# schematic.net
KiCad netlist of a schematic drawn in EAGLE
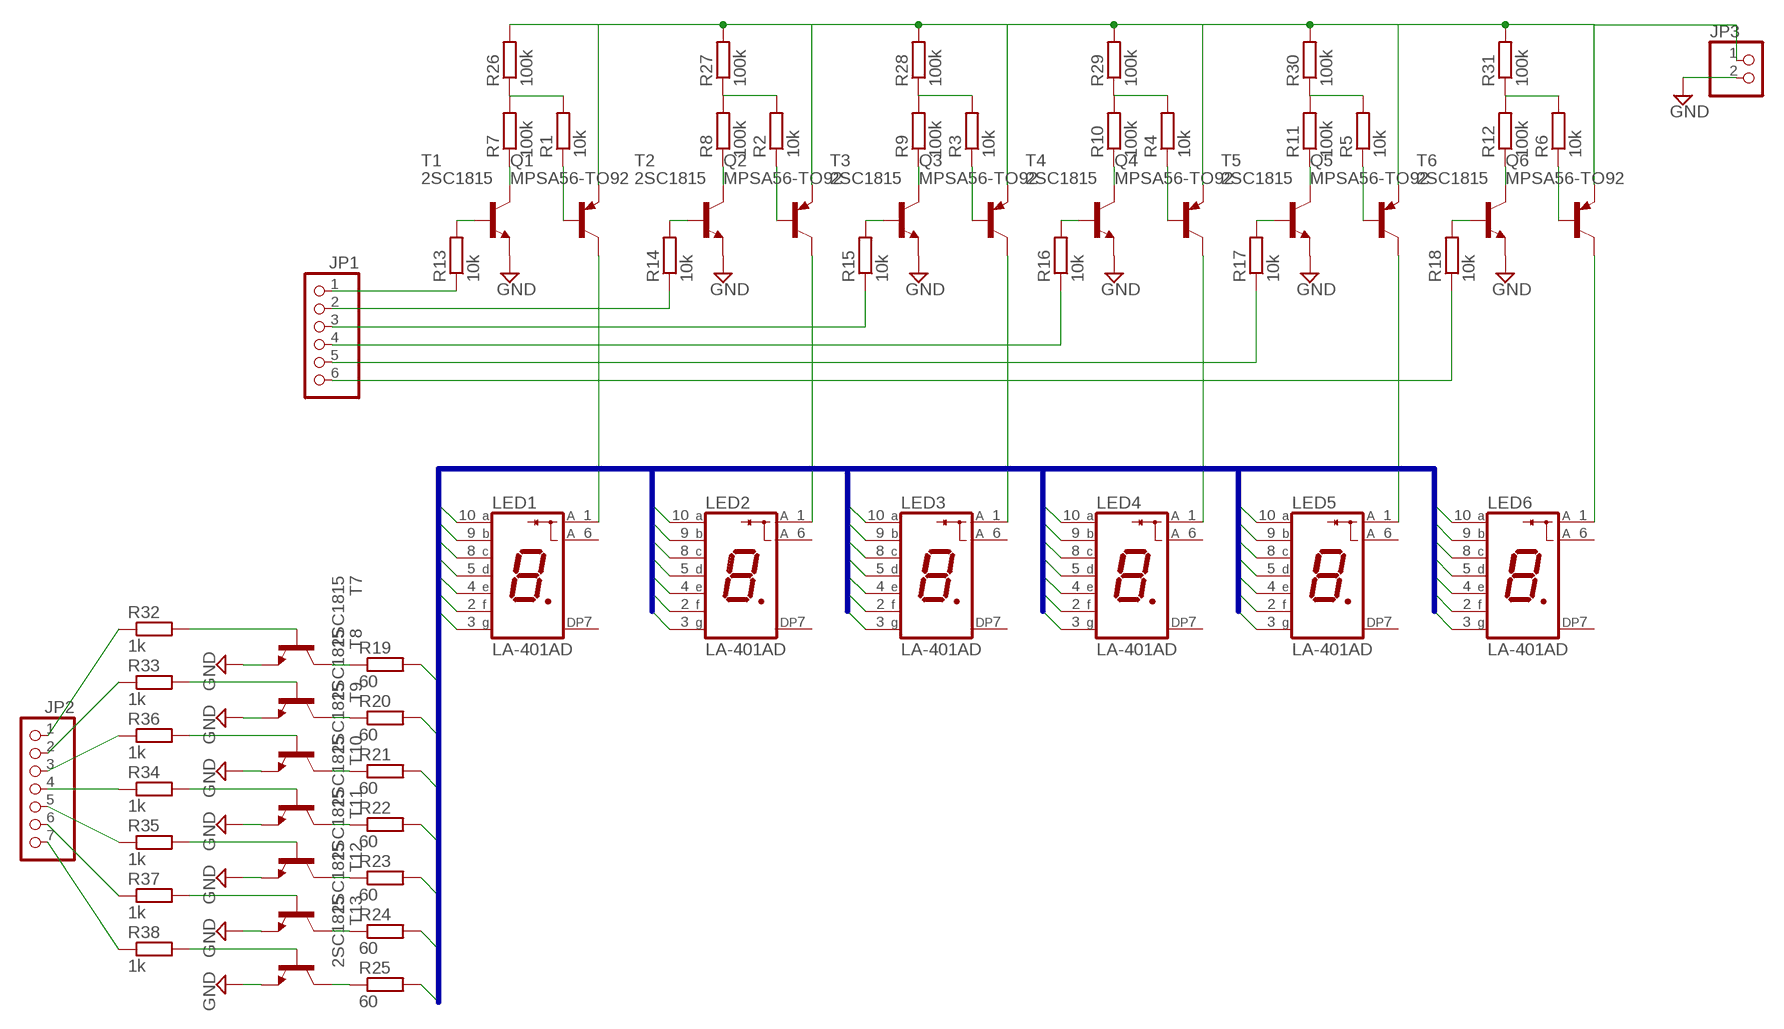
[diagram p0: schematic, sheet 1]

(export (version "E")
  (design (tool "Eeschema 10.0.6"))
  (components
    (comp (ref "JP1")
      (value "PINHD-1X6")
      (footprint "eagle-import:1X06")
      (libsource (lib "eagle-import") (part "PINHD-1X6"))
    )
    (comp (ref "JP2")
      (value "PINHD-1X7")
      (footprint "eagle-import:1X07")
      (libsource (lib "eagle-import") (part "PINHD-1X7"))
    )
    (comp (ref "JP3")
      (value "PINHD-1X2")
      (footprint "eagle-import:1X02")
      (libsource (lib "eagle-import") (part "PINHD-1X2"))
    )
    (comp (ref "LED1")
      (value "LA-401AD")
      (footprint "eagle-import:LA-401")
      (libsource (lib "eagle-import") (part "LA-401DA"))
    )
    (comp (ref "LED2")
      (value "LA-401AD")
      (footprint "eagle-import:LA-401")
      (libsource (lib "eagle-import") (part "LA-401DA"))
    )
    (comp (ref "LED3")
      (value "LA-401AD")
      (footprint "eagle-import:LA-401")
      (libsource (lib "eagle-import") (part "LA-401DA"))
    )
    (comp (ref "LED4")
      (value "LA-401AD")
      (footprint "eagle-import:LA-401")
      (libsource (lib "eagle-import") (part "LA-401DA"))
    )
    (comp (ref "LED5")
      (value "LA-401AD")
      (footprint "eagle-import:LA-401")
      (libsource (lib "eagle-import") (part "LA-401DA"))
    )
    (comp (ref "LED6")
      (value "LA-401AD")
      (footprint "eagle-import:LA-401")
      (libsource (lib "eagle-import") (part "LA-401DA"))
    )
    (comp (ref "Q1")
      (value "MPSA56-TO92")
      (footprint "eagle-import:TO92-CBE")
      (libsource (lib "eagle-import") (part "-?TO92MPSA56"))
    )
    (comp (ref "Q2")
      (value "MPSA56-TO92")
      (footprint "eagle-import:TO92-CBE")
      (libsource (lib "eagle-import") (part "-?TO92MPSA56"))
    )
    (comp (ref "Q3")
      (value "MPSA56-TO92")
      (footprint "eagle-import:TO92-CBE")
      (libsource (lib "eagle-import") (part "-?TO92MPSA56"))
    )
    (comp (ref "Q4")
      (value "MPSA56-TO92")
      (footprint "eagle-import:TO92-CBE")
      (libsource (lib "eagle-import") (part "-?TO92MPSA56"))
    )
    (comp (ref "Q5")
      (value "MPSA56-TO92")
      (footprint "eagle-import:TO92-CBE")
      (libsource (lib "eagle-import") (part "-?TO92MPSA56"))
    )
    (comp (ref "Q6")
      (value "MPSA56-TO92")
      (footprint "eagle-import:TO92-CBE")
      (libsource (lib "eagle-import") (part "-?TO92MPSA56"))
    )
    (comp (ref "R1")
      (value "10k")
      (footprint "eagle-import:0204_5")
      (libsource (lib "eagle-import") (part "R-EU_0204/5"))
    )
    (comp (ref "R2")
      (value "10k")
      (footprint "eagle-import:0204_5")
      (libsource (lib "eagle-import") (part "R-EU_0204/5"))
    )
    (comp (ref "R3")
      (value "10k")
      (footprint "eagle-import:0204_5")
      (libsource (lib "eagle-import") (part "R-EU_0204/5"))
    )
    (comp (ref "R4")
      (value "10k")
      (footprint "eagle-import:0204_5")
      (libsource (lib "eagle-import") (part "R-EU_0204/5"))
    )
    (comp (ref "R5")
      (value "10k")
      (footprint "eagle-import:0204_5")
      (libsource (lib "eagle-import") (part "R-EU_0204/5"))
    )
    (comp (ref "R6")
      (value "10k")
      (footprint "eagle-import:0204_5")
      (libsource (lib "eagle-import") (part "R-EU_0204/5"))
    )
    (comp (ref "R7")
      (value "100k")
      (footprint "eagle-import:0204_5")
      (libsource (lib "eagle-import") (part "R-EU_0204/5"))
    )
    (comp (ref "R8")
      (value "100k")
      (footprint "eagle-import:0204_5")
      (libsource (lib "eagle-import") (part "R-EU_0204/5"))
    )
    (comp (ref "R9")
      (value "100k")
      (footprint "eagle-import:0204_5")
      (libsource (lib "eagle-import") (part "R-EU_0204/5"))
    )
    (comp (ref "R10")
      (value "100k")
      (footprint "eagle-import:0204_5")
      (libsource (lib "eagle-import") (part "R-EU_0204/5"))
    )
    (comp (ref "R11")
      (value "100k")
      (footprint "eagle-import:0204_5")
      (libsource (lib "eagle-import") (part "R-EU_0204/5"))
    )
    (comp (ref "R12")
      (value "100k")
      (footprint "eagle-import:0204_5")
      (libsource (lib "eagle-import") (part "R-EU_0204/5"))
    )
    (comp (ref "R13")
      (value "10k")
      (footprint "eagle-import:0204_5")
      (libsource (lib "eagle-import") (part "R-EU_0204/5"))
    )
    (comp (ref "R14")
      (value "10k")
      (footprint "eagle-import:0204_5")
      (libsource (lib "eagle-import") (part "R-EU_0204/5"))
    )
    (comp (ref "R15")
      (value "10k")
      (footprint "eagle-import:0204_5")
      (libsource (lib "eagle-import") (part "R-EU_0204/5"))
    )
    (comp (ref "R16")
      (value "10k")
      (footprint "eagle-import:0204_5")
      (libsource (lib "eagle-import") (part "R-EU_0204/5"))
    )
    (comp (ref "R17")
      (value "10k")
      (footprint "eagle-import:0204_5")
      (libsource (lib "eagle-import") (part "R-EU_0204/5"))
    )
    (comp (ref "R18")
      (value "10k")
      (footprint "eagle-import:0204_5")
      (libsource (lib "eagle-import") (part "R-EU_0204/5"))
    )
    (comp (ref "R19")
      (value "60")
      (footprint "eagle-import:0204_5")
      (libsource (lib "eagle-import") (part "R-EU_0204/5"))
    )
    (comp (ref "R20")
      (value "60")
      (footprint "eagle-import:0204_5")
      (libsource (lib "eagle-import") (part "R-EU_0204/5"))
    )
    (comp (ref "R21")
      (value "60")
      (footprint "eagle-import:0204_5")
      (libsource (lib "eagle-import") (part "R-EU_0204/5"))
    )
    (comp (ref "R22")
      (value "60")
      (footprint "eagle-import:0204_5")
      (libsource (lib "eagle-import") (part "R-EU_0204/5"))
    )
    (comp (ref "R23")
      (value "60")
      (footprint "eagle-import:0204_5")
      (libsource (lib "eagle-import") (part "R-EU_0204/5"))
    )
    (comp (ref "R24")
      (value "60")
      (footprint "eagle-import:0204_5")
      (libsource (lib "eagle-import") (part "R-EU_0204/5"))
    )
    (comp (ref "R25")
      (value "60")
      (footprint "eagle-import:0204_5")
      (libsource (lib "eagle-import") (part "R-EU_0204/5"))
    )
    (comp (ref "R26")
      (value "100k")
      (footprint "eagle-import:0204_5")
      (libsource (lib "eagle-import") (part "R-EU_0204/5"))
    )
    (comp (ref "R27")
      (value "100k")
      (footprint "eagle-import:0204_5")
      (libsource (lib "eagle-import") (part "R-EU_0204/5"))
    )
    (comp (ref "R28")
      (value "100k")
      (footprint "eagle-import:0204_5")
      (libsource (lib "eagle-import") (part "R-EU_0204/5"))
    )
    (comp (ref "R29")
      (value "100k")
      (footprint "eagle-import:0204_5")
      (libsource (lib "eagle-import") (part "R-EU_0204/5"))
    )
    (comp (ref "R30")
      (value "100k")
      (footprint "eagle-import:0204_5")
      (libsource (lib "eagle-import") (part "R-EU_0204/5"))
    )
    (comp (ref "R31")
      (value "100k")
      (footprint "eagle-import:0204_5")
      (libsource (lib "eagle-import") (part "R-EU_0204/5"))
    )
    (comp (ref "R32")
      (value "1k")
      (footprint "eagle-import:0204_5")
      (libsource (lib "eagle-import") (part "R-EU_0204/5"))
    )
    (comp (ref "R33")
      (value "1k")
      (footprint "eagle-import:0204_5")
      (libsource (lib "eagle-import") (part "R-EU_0204/5"))
    )
    (comp (ref "R34")
      (value "1k")
      (footprint "eagle-import:0204_5")
      (libsource (lib "eagle-import") (part "R-EU_0204/5"))
    )
    (comp (ref "R35")
      (value "1k")
      (footprint "eagle-import:0204_5")
      (libsource (lib "eagle-import") (part "R-EU_0204/5"))
    )
    (comp (ref "R36")
      (value "1k")
      (footprint "eagle-import:0204_5")
      (libsource (lib "eagle-import") (part "R-EU_0204/5"))
    )
    (comp (ref "R37")
      (value "1k")
      (footprint "eagle-import:0204_5")
      (libsource (lib "eagle-import") (part "R-EU_0204/5"))
    )
    (comp (ref "R38")
      (value "1k")
      (footprint "eagle-import:0204_5")
      (libsource (lib "eagle-import") (part "R-EU_0204/5"))
    )
    (comp (ref "T1")
      (value "2SC1815")
      (footprint "eagle-import:TO92-ECB")
      (libsource (lib "eagle-import") (part "2SC1815"))
    )
    (comp (ref "T2")
      (value "2SC1815")
      (footprint "eagle-import:TO92-ECB")
      (libsource (lib "eagle-import") (part "2SC1815"))
    )
    (comp (ref "T3")
      (value "2SC1815")
      (footprint "eagle-import:TO92-ECB")
      (libsource (lib "eagle-import") (part "2SC1815"))
    )
    (comp (ref "T4")
      (value "2SC1815")
      (footprint "eagle-import:TO92-ECB")
      (libsource (lib "eagle-import") (part "2SC1815"))
    )
    (comp (ref "T5")
      (value "2SC1815")
      (footprint "eagle-import:TO92-ECB")
      (libsource (lib "eagle-import") (part "2SC1815"))
    )
    (comp (ref "T6")
      (value "2SC1815")
      (footprint "eagle-import:TO92-ECB")
      (libsource (lib "eagle-import") (part "2SC1815"))
    )
    (comp (ref "T7")
      (value "2SC1815")
      (footprint "eagle-import:TO92-ECB")
      (libsource (lib "eagle-import") (part "2SC1815"))
    )
    (comp (ref "T8")
      (value "2SC1815")
      (footprint "eagle-import:TO92-ECB")
      (libsource (lib "eagle-import") (part "2SC1815"))
    )
    (comp (ref "T9")
      (value "2SC1815")
      (footprint "eagle-import:TO92-ECB")
      (libsource (lib "eagle-import") (part "2SC1815"))
    )
    (comp (ref "T10")
      (value "2SC1815")
      (footprint "eagle-import:TO92-ECB")
      (libsource (lib "eagle-import") (part "2SC1815"))
    )
    (comp (ref "T11")
      (value "2SC1815")
      (footprint "eagle-import:TO92-ECB")
      (libsource (lib "eagle-import") (part "2SC1815"))
    )
    (comp (ref "T12")
      (value "2SC1815")
      (footprint "eagle-import:TO92-ECB")
      (libsource (lib "eagle-import") (part "2SC1815"))
    )
    (comp (ref "T13")
      (value "2SC1815")
      (footprint "eagle-import:TO92-ECB")
      (libsource (lib "eagle-import") (part "2SC1815"))
    )
  )
  (nets
    (net (code "1") (name "/SEGMENT1") (class "Default")
      (node (ref "LED1") (pin "3") (pinfunction "G_3") (pintype "passive"))
      (node (ref "LED2") (pin "3") (pinfunction "G_3") (pintype "passive"))
      (node (ref "LED3") (pin "3") (pinfunction "G_3") (pintype "passive"))
      (node (ref "LED4") (pin "3") (pinfunction "G_3") (pintype "passive"))
      (node (ref "LED5") (pin "3") (pinfunction "G_3") (pintype "passive"))
      (node (ref "LED6") (pin "3") (pinfunction "G_3") (pintype "passive"))
      (node (ref "R25") (pin "2") (pinfunction "2_2") (pintype "passive"))
    )
    (net (code "2") (name "/SEGMENT2") (class "Default")
      (node (ref "LED1") (pin "2") (pinfunction "F_2") (pintype "passive"))
      (node (ref "LED2") (pin "2") (pinfunction "F_2") (pintype "passive"))
      (node (ref "LED3") (pin "2") (pinfunction "F_2") (pintype "passive"))
      (node (ref "LED4") (pin "2") (pinfunction "F_2") (pintype "passive"))
      (node (ref "LED5") (pin "2") (pinfunction "F_2") (pintype "passive"))
      (node (ref "LED6") (pin "2") (pinfunction "F_2") (pintype "passive"))
      (node (ref "R24") (pin "2") (pinfunction "2_2") (pintype "passive"))
    )
    (net (code "3") (name "/SEGMENT3") (class "Default")
      (node (ref "LED1") (pin "4") (pinfunction "E_4") (pintype "passive"))
      (node (ref "LED2") (pin "4") (pinfunction "E_4") (pintype "passive"))
      (node (ref "LED3") (pin "4") (pinfunction "E_4") (pintype "passive"))
      (node (ref "LED4") (pin "4") (pinfunction "E_4") (pintype "passive"))
      (node (ref "LED5") (pin "4") (pinfunction "E_4") (pintype "passive"))
      (node (ref "LED6") (pin "4") (pinfunction "E_4") (pintype "passive"))
      (node (ref "R23") (pin "2") (pinfunction "2_2") (pintype "passive"))
    )
    (net (code "4") (name "/SEGMENT4") (class "Default")
      (node (ref "LED1") (pin "5") (pinfunction "D_5") (pintype "passive"))
      (node (ref "LED2") (pin "5") (pinfunction "D_5") (pintype "passive"))
      (node (ref "LED3") (pin "5") (pinfunction "D_5") (pintype "passive"))
      (node (ref "LED4") (pin "5") (pinfunction "D_5") (pintype "passive"))
      (node (ref "LED5") (pin "5") (pinfunction "D_5") (pintype "passive"))
      (node (ref "LED6") (pin "5") (pinfunction "D_5") (pintype "passive"))
      (node (ref "R22") (pin "2") (pinfunction "2_2") (pintype "passive"))
    )
    (net (code "5") (name "/SEGMENT5") (class "Default")
      (node (ref "LED1") (pin "8") (pinfunction "C_8") (pintype "passive"))
      (node (ref "LED2") (pin "8") (pinfunction "C_8") (pintype "passive"))
      (node (ref "LED3") (pin "8") (pinfunction "C_8") (pintype "passive"))
      (node (ref "LED4") (pin "8") (pinfunction "C_8") (pintype "passive"))
      (node (ref "LED5") (pin "8") (pinfunction "C_8") (pintype "passive"))
      (node (ref "LED6") (pin "8") (pinfunction "C_8") (pintype "passive"))
      (node (ref "R21") (pin "2") (pinfunction "2_2") (pintype "passive"))
    )
    (net (code "6") (name "/SEGMENT6") (class "Default")
      (node (ref "LED1") (pin "9") (pinfunction "B_9") (pintype "passive"))
      (node (ref "LED2") (pin "9") (pinfunction "B_9") (pintype "passive"))
      (node (ref "LED3") (pin "9") (pinfunction "B_9") (pintype "passive"))
      (node (ref "LED4") (pin "9") (pinfunction "B_9") (pintype "passive"))
      (node (ref "LED5") (pin "9") (pinfunction "B_9") (pintype "passive"))
      (node (ref "LED6") (pin "9") (pinfunction "B_9") (pintype "passive"))
      (node (ref "R20") (pin "2") (pinfunction "2_2") (pintype "passive"))
    )
    (net (code "7") (name "/SEGMENT7") (class "Default")
      (node (ref "LED1") (pin "10") (pinfunction "A_10") (pintype "passive"))
      (node (ref "LED2") (pin "10") (pinfunction "A_10") (pintype "passive"))
      (node (ref "LED3") (pin "10") (pinfunction "A_10") (pintype "passive"))
      (node (ref "LED4") (pin "10") (pinfunction "A_10") (pintype "passive"))
      (node (ref "LED5") (pin "10") (pinfunction "A_10") (pintype "passive"))
      (node (ref "LED6") (pin "10") (pinfunction "A_10") (pintype "passive"))
      (node (ref "R19") (pin "2") (pinfunction "2_2") (pintype "passive"))
    )
    (net (code "8") (name "GND") (class "Default")
      (node (ref "JP3") (pin "2") (pinfunction "2_2") (pintype "passive"))
      (node (ref "T1") (pin "E") (pinfunction "E_E") (pintype "passive"))
      (node (ref "T10") (pin "E") (pinfunction "E_E") (pintype "passive"))
      (node (ref "T11") (pin "E") (pinfunction "E_E") (pintype "passive"))
      (node (ref "T12") (pin "E") (pinfunction "E_E") (pintype "passive"))
      (node (ref "T13") (pin "E") (pinfunction "E_E") (pintype "passive"))
      (node (ref "T2") (pin "E") (pinfunction "E_E") (pintype "passive"))
      (node (ref "T3") (pin "E") (pinfunction "E_E") (pintype "passive"))
      (node (ref "T4") (pin "E") (pinfunction "E_E") (pintype "passive"))
      (node (ref "T5") (pin "E") (pinfunction "E_E") (pintype "passive"))
      (node (ref "T6") (pin "E") (pinfunction "E_E") (pintype "passive"))
      (node (ref "T7") (pin "E") (pinfunction "E_E") (pintype "passive"))
      (node (ref "T8") (pin "E") (pinfunction "E_E") (pintype "passive"))
      (node (ref "T9") (pin "E") (pinfunction "E_E") (pintype "passive"))
    )
    (net (code "9") (name "Net-(JP1-Pad1)") (class "Default")
      (node (ref "JP1") (pin "1") (pinfunction "1_1") (pintype "passive"))
      (node (ref "R13") (pin "1") (pinfunction "1_1") (pintype "passive"))
    )
    (net (code "10") (name "Net-(JP1-Pad2)") (class "Default")
      (node (ref "JP1") (pin "2") (pinfunction "2_2") (pintype "passive"))
      (node (ref "R14") (pin "1") (pinfunction "1_1") (pintype "passive"))
    )
    (net (code "11") (name "Net-(JP1-Pad3)") (class "Default")
      (node (ref "JP1") (pin "3") (pinfunction "3_3") (pintype "passive"))
      (node (ref "R15") (pin "1") (pinfunction "1_1") (pintype "passive"))
    )
    (net (code "12") (name "Net-(JP1-Pad4)") (class "Default")
      (node (ref "JP1") (pin "4") (pinfunction "4_4") (pintype "passive"))
      (node (ref "R16") (pin "1") (pinfunction "1_1") (pintype "passive"))
    )
    (net (code "13") (name "Net-(JP1-Pad5)") (class "Default")
      (node (ref "JP1") (pin "5") (pinfunction "5_5") (pintype "passive"))
      (node (ref "R17") (pin "1") (pinfunction "1_1") (pintype "passive"))
    )
    (net (code "14") (name "Net-(JP1-Pad6)") (class "Default")
      (node (ref "JP1") (pin "6") (pinfunction "6_6") (pintype "passive"))
      (node (ref "R18") (pin "1") (pinfunction "1_1") (pintype "passive"))
    )
    (net (code "15") (name "Net-(JP2-Pad1)") (class "Default")
      (node (ref "JP2") (pin "1") (pinfunction "1_1") (pintype "passive"))
      (node (ref "R32") (pin "1") (pinfunction "1_1") (pintype "passive"))
    )
    (net (code "16") (name "Net-(JP2-Pad2)") (class "Default")
      (node (ref "JP2") (pin "2") (pinfunction "2_2") (pintype "passive"))
      (node (ref "R33") (pin "1") (pinfunction "1_1") (pintype "passive"))
    )
    (net (code "17") (name "Net-(JP2-Pad3)") (class "Default")
      (node (ref "JP2") (pin "3") (pinfunction "3_3") (pintype "passive"))
      (node (ref "R36") (pin "1") (pinfunction "1_1") (pintype "passive"))
    )
    (net (code "18") (name "Net-(JP2-Pad4)") (class "Default")
      (node (ref "JP2") (pin "4") (pinfunction "4_4") (pintype "passive"))
      (node (ref "R34") (pin "1") (pinfunction "1_1") (pintype "passive"))
    )
    (net (code "19") (name "Net-(JP2-Pad5)") (class "Default")
      (node (ref "JP2") (pin "5") (pinfunction "5_5") (pintype "passive"))
      (node (ref "R35") (pin "1") (pinfunction "1_1") (pintype "passive"))
    )
    (net (code "20") (name "Net-(JP2-Pad6)") (class "Default")
      (node (ref "JP2") (pin "6") (pinfunction "6_6") (pintype "passive"))
      (node (ref "R37") (pin "1") (pinfunction "1_1") (pintype "passive"))
    )
    (net (code "21") (name "Net-(JP2-Pad7)") (class "Default")
      (node (ref "JP2") (pin "7") (pinfunction "7_7") (pintype "passive"))
      (node (ref "R38") (pin "1") (pinfunction "1_1") (pintype "passive"))
    )
    (net (code "22") (name "Net-(JP3-Pad1)") (class "Default")
      (node (ref "JP3") (pin "1") (pinfunction "1_1") (pintype "passive"))
      (node (ref "Q1") (pin "E") (pinfunction "E_E") (pintype "passive"))
      (node (ref "Q2") (pin "E") (pinfunction "E_E") (pintype "passive"))
      (node (ref "Q3") (pin "E") (pinfunction "E_E") (pintype "passive"))
      (node (ref "Q4") (pin "E") (pinfunction "E_E") (pintype "passive"))
      (node (ref "Q5") (pin "E") (pinfunction "E_E") (pintype "passive"))
      (node (ref "Q6") (pin "E") (pinfunction "E_E") (pintype "passive"))
      (node (ref "R26") (pin "2") (pinfunction "2_2") (pintype "passive"))
      (node (ref "R27") (pin "2") (pinfunction "2_2") (pintype "passive"))
      (node (ref "R28") (pin "2") (pinfunction "2_2") (pintype "passive"))
      (node (ref "R29") (pin "2") (pinfunction "2_2") (pintype "passive"))
      (node (ref "R30") (pin "2") (pinfunction "2_2") (pintype "passive"))
      (node (ref "R31") (pin "2") (pinfunction "2_2") (pintype "passive"))
    )
    (net (code "23") (name "Net-(LED1-A-Pad1)") (class "Default")
      (node (ref "LED1") (pin "1") (pinfunction "A_1") (pintype "passive"))
      (node (ref "Q1") (pin "C") (pinfunction "C_C") (pintype "passive"))
    )
    (net (code "24") (name "Net-(LED2-A-Pad1)") (class "Default")
      (node (ref "LED2") (pin "1") (pinfunction "A_1") (pintype "passive"))
      (node (ref "Q2") (pin "C") (pinfunction "C_C") (pintype "passive"))
    )
    (net (code "25") (name "Net-(LED3-A-Pad1)") (class "Default")
      (node (ref "LED3") (pin "1") (pinfunction "A_1") (pintype "passive"))
      (node (ref "Q3") (pin "C") (pinfunction "C_C") (pintype "passive"))
    )
    (net (code "26") (name "Net-(LED4-A-Pad1)") (class "Default")
      (node (ref "LED4") (pin "1") (pinfunction "A_1") (pintype "passive"))
      (node (ref "Q4") (pin "C") (pinfunction "C_C") (pintype "passive"))
    )
    (net (code "27") (name "Net-(LED5-A-Pad1)") (class "Default")
      (node (ref "LED5") (pin "1") (pinfunction "A_1") (pintype "passive"))
      (node (ref "Q5") (pin "C") (pinfunction "C_C") (pintype "passive"))
    )
    (net (code "28") (name "Net-(LED6-A-Pad1)") (class "Default")
      (node (ref "LED6") (pin "1") (pinfunction "A_1") (pintype "passive"))
      (node (ref "Q6") (pin "C") (pinfunction "C_C") (pintype "passive"))
    )
    (net (code "29") (name "Net-(Q1-PadB)") (class "Default")
      (node (ref "Q1") (pin "B") (pinfunction "B_B") (pintype "passive"))
      (node (ref "R1") (pin "1") (pinfunction "1_1") (pintype "passive"))
    )
    (net (code "30") (name "Net-(Q2-PadB)") (class "Default")
      (node (ref "Q2") (pin "B") (pinfunction "B_B") (pintype "passive"))
      (node (ref "R2") (pin "1") (pinfunction "1_1") (pintype "passive"))
    )
    (net (code "31") (name "Net-(Q3-PadB)") (class "Default")
      (node (ref "Q3") (pin "B") (pinfunction "B_B") (pintype "passive"))
      (node (ref "R3") (pin "1") (pinfunction "1_1") (pintype "passive"))
    )
    (net (code "32") (name "Net-(Q4-PadB)") (class "Default")
      (node (ref "Q4") (pin "B") (pinfunction "B_B") (pintype "passive"))
      (node (ref "R4") (pin "1") (pinfunction "1_1") (pintype "passive"))
    )
    (net (code "33") (name "Net-(Q5-PadB)") (class "Default")
      (node (ref "Q5") (pin "B") (pinfunction "B_B") (pintype "passive"))
      (node (ref "R5") (pin "1") (pinfunction "1_1") (pintype "passive"))
    )
    (net (code "34") (name "Net-(Q6-PadB)") (class "Default")
      (node (ref "Q6") (pin "B") (pinfunction "B_B") (pintype "passive"))
      (node (ref "R6") (pin "1") (pinfunction "1_1") (pintype "passive"))
    )
    (net (code "35") (name "Net-(R1-Pad2)") (class "Default")
      (node (ref "R1") (pin "2") (pinfunction "2_2") (pintype "passive"))
      (node (ref "R26") (pin "1") (pinfunction "1_1") (pintype "passive"))
      (node (ref "R7") (pin "2") (pinfunction "2_2") (pintype "passive"))
    )
    (net (code "36") (name "Net-(R2-Pad2)") (class "Default")
      (node (ref "R2") (pin "2") (pinfunction "2_2") (pintype "passive"))
      (node (ref "R27") (pin "1") (pinfunction "1_1") (pintype "passive"))
      (node (ref "R8") (pin "2") (pinfunction "2_2") (pintype "passive"))
    )
    (net (code "37") (name "Net-(R7-Pad1)") (class "Default")
      (node (ref "R7") (pin "1") (pinfunction "1_1") (pintype "passive"))
      (node (ref "T1") (pin "C") (pinfunction "C_C") (pintype "passive"))
    )
    (net (code "38") (name "Net-(R8-Pad1)") (class "Default")
      (node (ref "R8") (pin "1") (pinfunction "1_1") (pintype "passive"))
      (node (ref "T2") (pin "C") (pinfunction "C_C") (pintype "passive"))
    )
    (net (code "39") (name "Net-(R9-Pad1)") (class "Default")
      (node (ref "R9") (pin "1") (pinfunction "1_1") (pintype "passive"))
      (node (ref "T3") (pin "C") (pinfunction "C_C") (pintype "passive"))
    )
    (net (code "40") (name "Net-(R10-Pad1)") (class "Default")
      (node (ref "R10") (pin "1") (pinfunction "1_1") (pintype "passive"))
      (node (ref "T4") (pin "C") (pinfunction "C_C") (pintype "passive"))
    )
    (net (code "41") (name "Net-(R10-Pad2)") (class "Default")
      (node (ref "R10") (pin "2") (pinfunction "2_2") (pintype "passive"))
      (node (ref "R29") (pin "1") (pinfunction "1_1") (pintype "passive"))
      (node (ref "R4") (pin "2") (pinfunction "2_2") (pintype "passive"))
    )
    (net (code "42") (name "Net-(R11-Pad1)") (class "Default")
      (node (ref "R11") (pin "1") (pinfunction "1_1") (pintype "passive"))
      (node (ref "T5") (pin "C") (pinfunction "C_C") (pintype "passive"))
    )
    (net (code "43") (name "Net-(R11-Pad2)") (class "Default")
      (node (ref "R11") (pin "2") (pinfunction "2_2") (pintype "passive"))
      (node (ref "R30") (pin "1") (pinfunction "1_1") (pintype "passive"))
      (node (ref "R5") (pin "2") (pinfunction "2_2") (pintype "passive"))
    )
    (net (code "44") (name "Net-(R12-Pad1)") (class "Default")
      (node (ref "R12") (pin "1") (pinfunction "1_1") (pintype "passive"))
      (node (ref "T6") (pin "C") (pinfunction "C_C") (pintype "passive"))
    )
    (net (code "45") (name "Net-(R12-Pad2)") (class "Default")
      (node (ref "R12") (pin "2") (pinfunction "2_2") (pintype "passive"))
      (node (ref "R31") (pin "1") (pinfunction "1_1") (pintype "passive"))
      (node (ref "R6") (pin "2") (pinfunction "2_2") (pintype "passive"))
    )
    (net (code "46") (name "Net-(R13-Pad2)") (class "Default")
      (node (ref "R13") (pin "2") (pinfunction "2_2") (pintype "passive"))
      (node (ref "T1") (pin "B") (pinfunction "B_B") (pintype "passive"))
    )
    (net (code "47") (name "Net-(R14-Pad2)") (class "Default")
      (node (ref "R14") (pin "2") (pinfunction "2_2") (pintype "passive"))
      (node (ref "T2") (pin "B") (pinfunction "B_B") (pintype "passive"))
    )
    (net (code "48") (name "Net-(R15-Pad2)") (class "Default")
      (node (ref "R15") (pin "2") (pinfunction "2_2") (pintype "passive"))
      (node (ref "T3") (pin "B") (pinfunction "B_B") (pintype "passive"))
    )
    (net (code "49") (name "Net-(R16-Pad2)") (class "Default")
      (node (ref "R16") (pin "2") (pinfunction "2_2") (pintype "passive"))
      (node (ref "T4") (pin "B") (pinfunction "B_B") (pintype "passive"))
    )
    (net (code "50") (name "Net-(R17-Pad2)") (class "Default")
      (node (ref "R17") (pin "2") (pinfunction "2_2") (pintype "passive"))
      (node (ref "T5") (pin "B") (pinfunction "B_B") (pintype "passive"))
    )
    (net (code "51") (name "Net-(R18-Pad2)") (class "Default")
      (node (ref "R18") (pin "2") (pinfunction "2_2") (pintype "passive"))
      (node (ref "T6") (pin "B") (pinfunction "B_B") (pintype "passive"))
    )
    (net (code "52") (name "Net-(R19-Pad1)") (class "Default")
      (node (ref "R19") (pin "1") (pinfunction "1_1") (pintype "passive"))
      (node (ref "T7") (pin "C") (pinfunction "C_C") (pintype "passive"))
    )
    (net (code "53") (name "Net-(R20-Pad1)") (class "Default")
      (node (ref "R20") (pin "1") (pinfunction "1_1") (pintype "passive"))
      (node (ref "T8") (pin "C") (pinfunction "C_C") (pintype "passive"))
    )
    (net (code "54") (name "Net-(R21-Pad1)") (class "Default")
      (node (ref "R21") (pin "1") (pinfunction "1_1") (pintype "passive"))
      (node (ref "T9") (pin "C") (pinfunction "C_C") (pintype "passive"))
    )
    (net (code "55") (name "Net-(R22-Pad1)") (class "Default")
      (node (ref "R22") (pin "1") (pinfunction "1_1") (pintype "passive"))
      (node (ref "T10") (pin "C") (pinfunction "C_C") (pintype "passive"))
    )
    (net (code "56") (name "Net-(R23-Pad1)") (class "Default")
      (node (ref "R23") (pin "1") (pinfunction "1_1") (pintype "passive"))
      (node (ref "T11") (pin "C") (pinfunction "C_C") (pintype "passive"))
    )
    (net (code "57") (name "Net-(R24-Pad1)") (class "Default")
      (node (ref "R24") (pin "1") (pinfunction "1_1") (pintype "passive"))
      (node (ref "T12") (pin "C") (pinfunction "C_C") (pintype "passive"))
    )
    (net (code "58") (name "Net-(R25-Pad1)") (class "Default")
      (node (ref "R25") (pin "1") (pinfunction "1_1") (pintype "passive"))
      (node (ref "T13") (pin "C") (pinfunction "C_C") (pintype "passive"))
    )
    (net (code "59") (name "Net-(R28-Pad1)") (class "Default")
      (node (ref "R28") (pin "1") (pinfunction "1_1") (pintype "passive"))
      (node (ref "R3") (pin "2") (pinfunction "2_2") (pintype "passive"))
      (node (ref "R9") (pin "2") (pinfunction "2_2") (pintype "passive"))
    )
    (net (code "60") (name "Net-(R32-Pad2)") (class "Default")
      (node (ref "R32") (pin "2") (pinfunction "2_2") (pintype "passive"))
      (node (ref "T7") (pin "B") (pinfunction "B_B") (pintype "passive"))
    )
    (net (code "61") (name "Net-(R33-Pad2)") (class "Default")
      (node (ref "R33") (pin "2") (pinfunction "2_2") (pintype "passive"))
      (node (ref "T8") (pin "B") (pinfunction "B_B") (pintype "passive"))
    )
    (net (code "62") (name "Net-(R34-Pad2)") (class "Default")
      (node (ref "R34") (pin "2") (pinfunction "2_2") (pintype "passive"))
      (node (ref "T10") (pin "B") (pinfunction "B_B") (pintype "passive"))
    )
    (net (code "63") (name "Net-(R35-Pad2)") (class "Default")
      (node (ref "R35") (pin "2") (pinfunction "2_2") (pintype "passive"))
      (node (ref "T11") (pin "B") (pinfunction "B_B") (pintype "passive"))
    )
    (net (code "64") (name "Net-(R36-Pad2)") (class "Default")
      (node (ref "R36") (pin "2") (pinfunction "2_2") (pintype "passive"))
      (node (ref "T9") (pin "B") (pinfunction "B_B") (pintype "passive"))
    )
    (net (code "65") (name "Net-(R37-Pad2)") (class "Default")
      (node (ref "R37") (pin "2") (pinfunction "2_2") (pintype "passive"))
      (node (ref "T12") (pin "B") (pinfunction "B_B") (pintype "passive"))
    )
    (net (code "66") (name "Net-(R38-Pad2)") (class "Default")
      (node (ref "R38") (pin "2") (pinfunction "2_2") (pintype "passive"))
      (node (ref "T13") (pin "B") (pinfunction "B_B") (pintype "passive"))
    )
    (net (code "67") (name "unconnected-(LED1-A-Pad6)") (class "Default")
      (node (ref "LED1") (pin "6") (pinfunction "A_6") (pintype "passive"))
    )
    (net (code "68") (name "unconnected-(LED1-DP-Pad7)") (class "Default")
      (node (ref "LED1") (pin "7") (pinfunction "DP_7") (pintype "passive"))
    )
    (net (code "69") (name "unconnected-(LED2-A-Pad6)") (class "Default")
      (node (ref "LED2") (pin "6") (pinfunction "A_6") (pintype "passive"))
    )
    (net (code "70") (name "unconnected-(LED2-DP-Pad7)") (class "Default")
      (node (ref "LED2") (pin "7") (pinfunction "DP_7") (pintype "passive"))
    )
    (net (code "71") (name "unconnected-(LED3-A-Pad6)") (class "Default")
      (node (ref "LED3") (pin "6") (pinfunction "A_6") (pintype "passive"))
    )
    (net (code "72") (name "unconnected-(LED3-DP-Pad7)") (class "Default")
      (node (ref "LED3") (pin "7") (pinfunction "DP_7") (pintype "passive"))
    )
    (net (code "73") (name "unconnected-(LED4-A-Pad6)") (class "Default")
      (node (ref "LED4") (pin "6") (pinfunction "A_6") (pintype "passive"))
    )
    (net (code "74") (name "unconnected-(LED4-DP-Pad7)") (class "Default")
      (node (ref "LED4") (pin "7") (pinfunction "DP_7") (pintype "passive"))
    )
    (net (code "75") (name "unconnected-(LED5-A-Pad6)") (class "Default")
      (node (ref "LED5") (pin "6") (pinfunction "A_6") (pintype "passive"))
    )
    (net (code "76") (name "unconnected-(LED5-DP-Pad7)") (class "Default")
      (node (ref "LED5") (pin "7") (pinfunction "DP_7") (pintype "passive"))
    )
    (net (code "77") (name "unconnected-(LED6-A-Pad6)") (class "Default")
      (node (ref "LED6") (pin "6") (pinfunction "A_6") (pintype "passive"))
    )
    (net (code "78") (name "unconnected-(LED6-DP-Pad7)") (class "Default")
      (node (ref "LED6") (pin "7") (pinfunction "DP_7") (pintype "passive"))
    )
  )
)
